# board.net
KiCad netlist of a schematic drawn in EAGLE
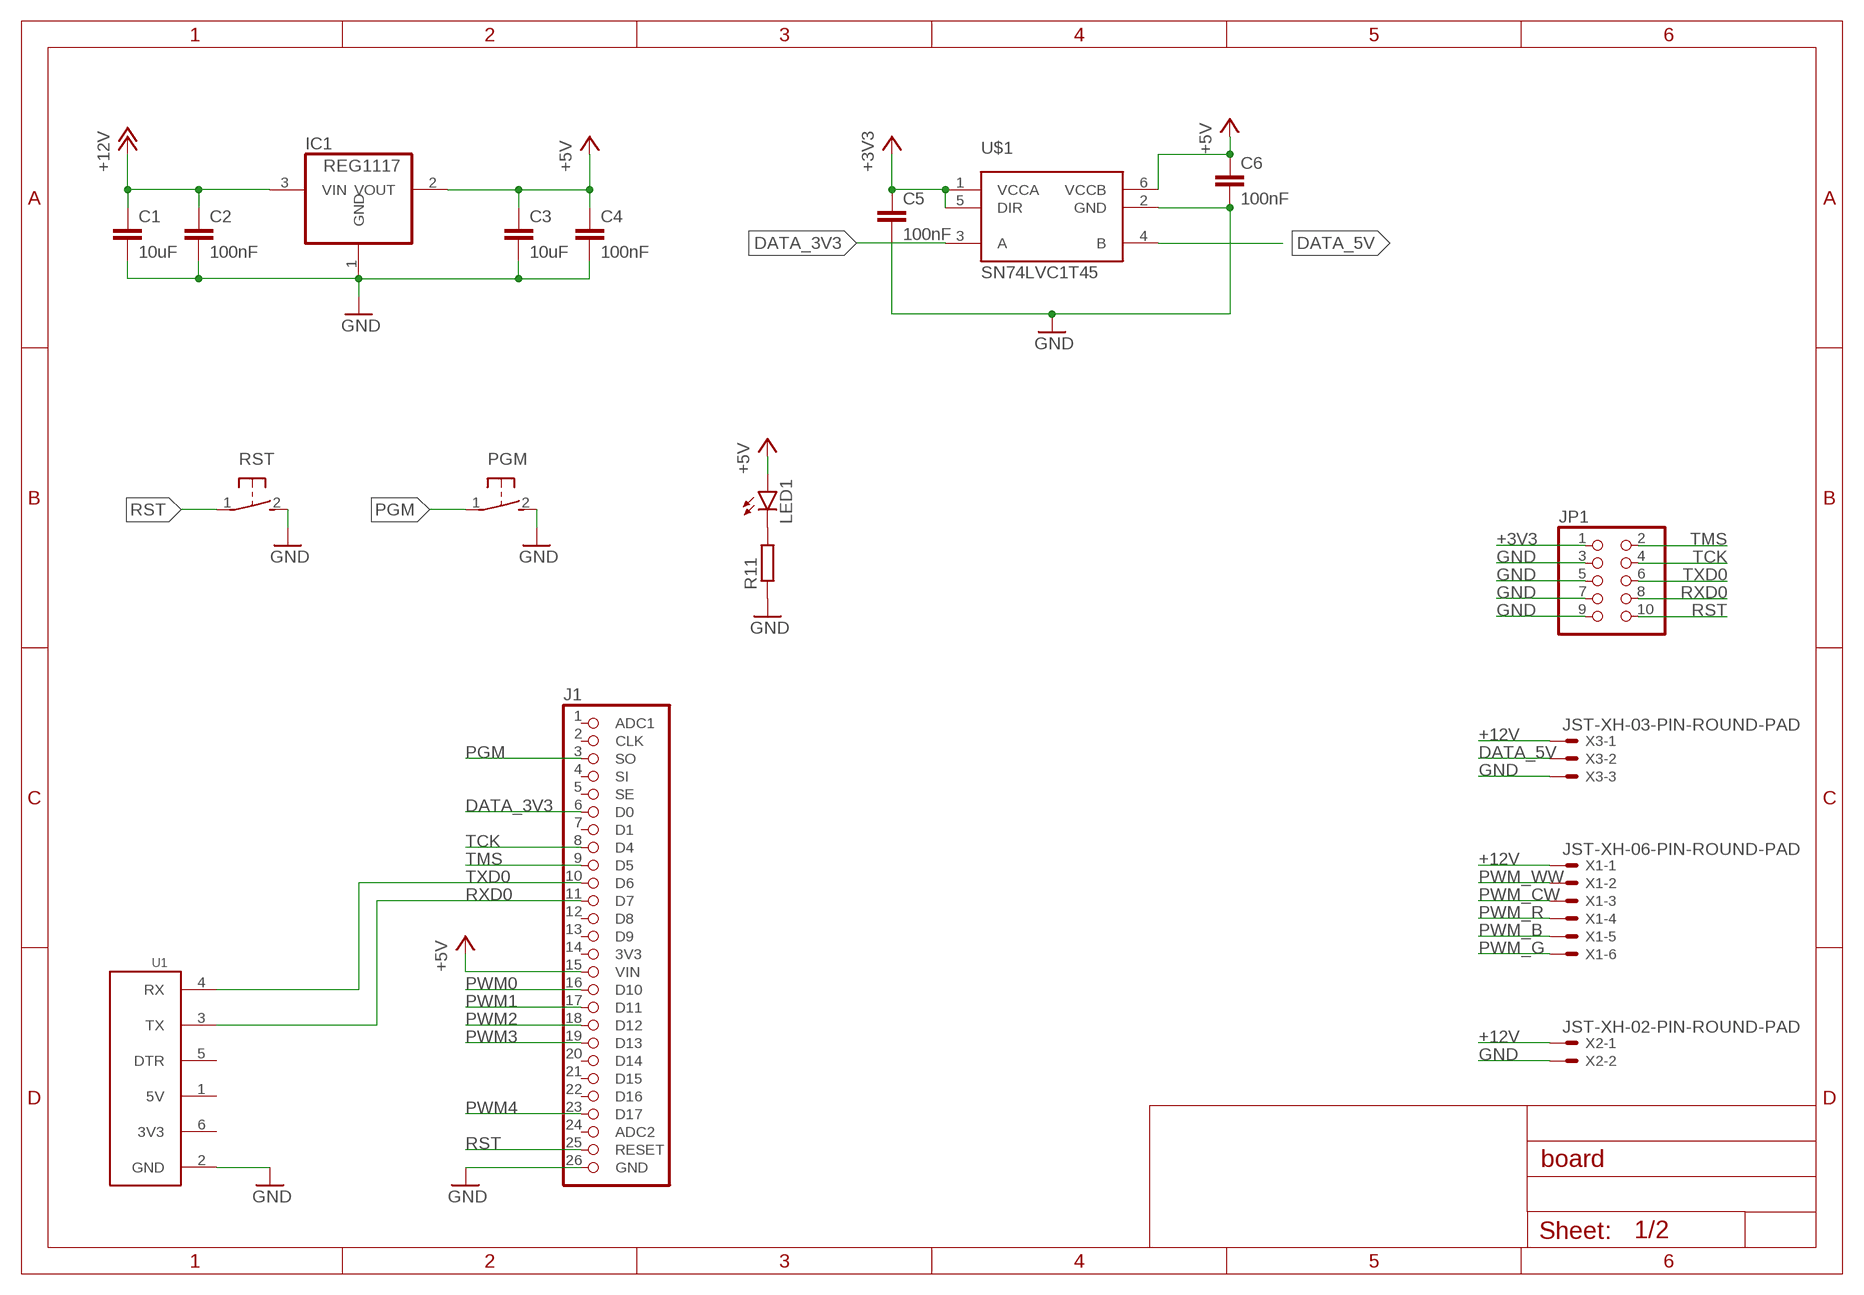
[diagram p0: schematic, sheet 1]
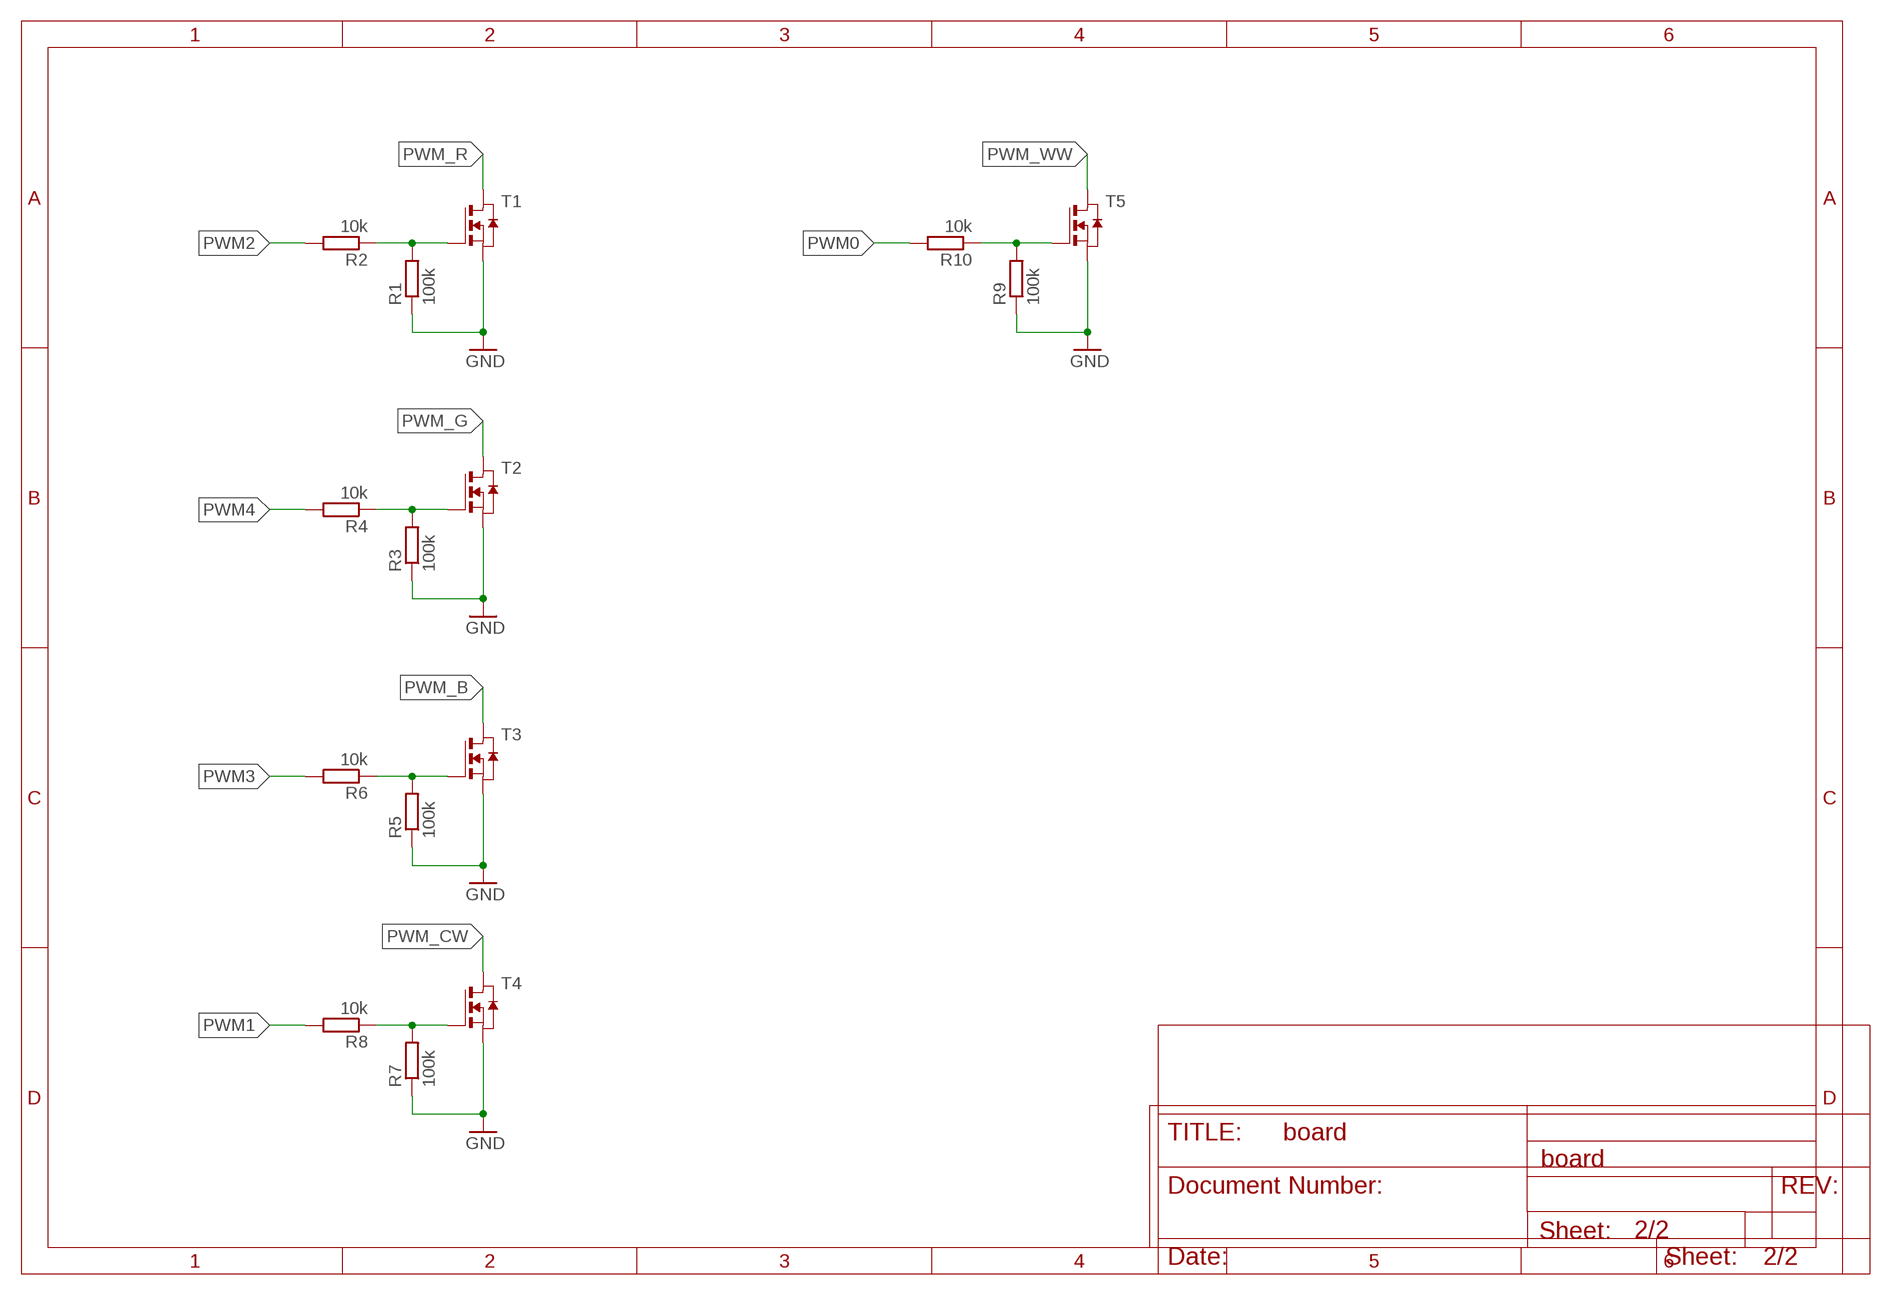
[diagram p1: schematic, sheet 2]

(export (version "E")
  (design (tool "Eeschema 10.0.6"))
  (components
    (comp (ref "C1")
      (value "10uF")
      (footprint "eagle-import:C0603")
      (libsource (lib "eagle-import") (part "C-EUC0603"))
    )
    (comp (ref "C2")
      (value "100nF")
      (footprint "eagle-import:C0603")
      (libsource (lib "eagle-import") (part "C-EUC0603"))
    )
    (comp (ref "C3")
      (value "10uF")
      (footprint "eagle-import:C0603")
      (libsource (lib "eagle-import") (part "C-EUC0603"))
    )
    (comp (ref "C4")
      (value "100nF")
      (footprint "eagle-import:C0603")
      (libsource (lib "eagle-import") (part "C-EUC0603"))
    )
    (comp (ref "C5")
      (value "100nF")
      (footprint "eagle-import:C0603")
      (libsource (lib "eagle-import") (part "C-EUC0603"))
    )
    (comp (ref "C6")
      (value "100nF")
      (footprint "eagle-import:C0603")
      (libsource (lib "eagle-import") (part "C-EUC0603"))
    )
    (comp (ref "IC1")
      (value "REG1117")
      (footprint "eagle-import:SOT223")
      (libsource (lib "eagle-import") (part "REG1117"))
    )
    (comp (ref "J1")
      (value "E75-2G4M20S-SOCKET")
      (footprint "eagle-import:E75-2G4M20S-SOCKET")
      (libsource (lib "eagle-import") (part "E75-2G4M20S-SOCKET"))
    )
    (comp (ref "JP1")
      (value "PINHD-2X5")
      (footprint "eagle-import:2X05")
      (libsource (lib "eagle-import") (part "PINHD-2X5"))
    )
    (comp (ref "LED1")
      (value "LEDCHIP-LED0603")
      (footprint "eagle-import:CHIP-LED0603")
      (libsource (lib "eagle-import") (part "LEDCHIP-LED0603"))
    )
    (comp (ref "PGM")
      (value "BUTTON3X4")
      (footprint "eagle-import:BUTTON3X4")
      (libsource (lib "eagle-import") (part "BUTTON3X4"))
    )
    (comp (ref "R11")
      (value "R-EU_R0603")
      (footprint "eagle-import:R0603")
      (libsource (lib "eagle-import") (part "R-EU_R0603"))
    )
    (comp (ref "RST")
      (value "BUTTON3X4")
      (footprint "eagle-import:BUTTON3X4")
      (libsource (lib "eagle-import") (part "BUTTON3X4"))
    )
    (comp (ref "U$1")
      (value "SN74LVC1T45")
      (footprint "eagle-import:SOT23-6")
      (fields (field (name "MF") "Texas Instruments"))
      (libsource (lib "eagle-import") (part "SN74LVC1T45"))
    )
    (comp (ref "U1")
      (value "CP2102-BOARD")
      (footprint "eagle-import:CP2102-BOARD")
      (libsource (lib "eagle-import") (part "CP2102-BOARD"))
    )
    (comp (ref "X1")
      (value "JST-XH-06-PIN-ROUND-PAD")
      (footprint "eagle-import:JST-XH-06-PACKAGE-ROUND-PAD")
      (libsource (lib "eagle-import") (part "JST-XH-06-PIN-ROUND-PAD"))
    )
    (comp (ref "X2")
      (value "JST-XH-02-PIN-ROUND-PAD")
      (footprint "eagle-import:JST-XH-02-PACKAGE-ROUND-PAD")
      (libsource (lib "eagle-import") (part "JST-XH-02-PIN-ROUND-PAD"))
    )
    (comp (ref "X3")
      (value "JST-XH-03-PIN-ROUND-PAD")
      (footprint "eagle-import:JST-XH-03-PACKAGE-ROUND-PAD")
      (libsource (lib "eagle-import") (part "JST-XH-03-PIN-ROUND-PAD"))
    )
    (comp (ref "R1")
      (value "100k")
      (footprint "eagle-import:R0603")
      (libsource (lib "eagle-import") (part "R-EU_R0603"))
    )
    (comp (ref "R2")
      (value "10k")
      (footprint "eagle-import:R0603")
      (libsource (lib "eagle-import") (part "R-EU_R0603"))
    )
    (comp (ref "R3")
      (value "100k")
      (footprint "eagle-import:R0603")
      (libsource (lib "eagle-import") (part "R-EU_R0603"))
    )
    (comp (ref "R4")
      (value "10k")
      (footprint "eagle-import:R0603")
      (libsource (lib "eagle-import") (part "R-EU_R0603"))
    )
    (comp (ref "R5")
      (value "100k")
      (footprint "eagle-import:R0603")
      (libsource (lib "eagle-import") (part "R-EU_R0603"))
    )
    (comp (ref "R6")
      (value "10k")
      (footprint "eagle-import:R0603")
      (libsource (lib "eagle-import") (part "R-EU_R0603"))
    )
    (comp (ref "R7")
      (value "100k")
      (footprint "eagle-import:R0603")
      (libsource (lib "eagle-import") (part "R-EU_R0603"))
    )
    (comp (ref "R8")
      (value "10k")
      (footprint "eagle-import:R0603")
      (libsource (lib "eagle-import") (part "R-EU_R0603"))
    )
    (comp (ref "R9")
      (value "100k")
      (footprint "eagle-import:R0603")
      (libsource (lib "eagle-import") (part "R-EU_R0603"))
    )
    (comp (ref "R10")
      (value "10k")
      (footprint "eagle-import:R0603")
      (libsource (lib "eagle-import") (part "R-EU_R0603"))
    )
    (comp (ref "T1")
      (value "NMOSSOT23")
      (footprint "eagle-import:SOT-23")
      (libsource (lib "eagle-import") (part "NMOSSOT23"))
    )
    (comp (ref "T2")
      (value "NMOSSOT23")
      (footprint "eagle-import:SOT-23")
      (libsource (lib "eagle-import") (part "NMOSSOT23"))
    )
    (comp (ref "T3")
      (value "NMOSSOT23")
      (footprint "eagle-import:SOT-23")
      (libsource (lib "eagle-import") (part "NMOSSOT23"))
    )
    (comp (ref "T4")
      (value "NMOSSOT23")
      (footprint "eagle-import:SOT-23")
      (libsource (lib "eagle-import") (part "NMOSSOT23"))
    )
    (comp (ref "T5")
      (value "NMOSSOT23")
      (footprint "eagle-import:SOT-23")
      (libsource (lib "eagle-import") (part "NMOSSOT23"))
    )
  )
  (nets
    (net (code "1") (name "+3V3") (class "Default")
      (node (ref "C5") (pin "1") (pinfunction "1_1") (pintype "passive"))
      (node (ref "JP1") (pin "1") (pinfunction "1_1") (pintype "passive"))
      (node (ref "U$1") (pin "1") (pinfunction "VCCA_1") (pintype "power_in"))
      (node (ref "U$1") (pin "5") (pinfunction "DIR_5") (pintype "input"))
    )
    (net (code "2") (name "+5V") (class "Default")
      (node (ref "C3") (pin "1") (pinfunction "1_1") (pintype "passive"))
      (node (ref "C4") (pin "1") (pinfunction "1_1") (pintype "passive"))
      (node (ref "C6") (pin "1") (pinfunction "1_1") (pintype "passive"))
      (node (ref "IC1") (pin "2") (pinfunction "VOUT_2") (pintype "output"))
      (node (ref "J1") (pin "15") (pinfunction "VIN_15") (pintype "passive"))
      (node (ref "LED1") (pin "A") (pinfunction "A_A") (pintype "passive"))
      (node (ref "U$1") (pin "6") (pinfunction "VCCB_6") (pintype "power_in"))
    )
    (net (code "3") (name "+12V") (class "Default")
      (node (ref "C1") (pin "1") (pinfunction "1_1") (pintype "passive"))
      (node (ref "C2") (pin "1") (pinfunction "1_1") (pintype "passive"))
      (node (ref "IC1") (pin "3") (pinfunction "VIN_3") (pintype "input"))
      (node (ref "X1") (pin "1") (pinfunction "S_1") (pintype "passive"))
      (node (ref "X2") (pin "1") (pinfunction "S_1") (pintype "passive"))
      (node (ref "X3") (pin "1") (pinfunction "S_1") (pintype "passive"))
    )
    (net (code "4") (name "DATA_3V3") (class "Default")
      (node (ref "J1") (pin "6") (pinfunction "D0_6") (pintype "passive"))
      (node (ref "U$1") (pin "3") (pinfunction "A_3") (pintype "bidirectional"))
    )
    (net (code "5") (name "DATA_5V") (class "Default")
      (node (ref "U$1") (pin "4") (pinfunction "B_4") (pintype "bidirectional"))
      (node (ref "X3") (pin "2") (pinfunction "S_2") (pintype "passive"))
    )
    (net (code "6") (name "GND") (class "Default")
      (node (ref "C1") (pin "2") (pinfunction "2_2") (pintype "passive"))
      (node (ref "C2") (pin "2") (pinfunction "2_2") (pintype "passive"))
      (node (ref "C3") (pin "2") (pinfunction "2_2") (pintype "passive"))
      (node (ref "C4") (pin "2") (pinfunction "2_2") (pintype "passive"))
      (node (ref "C5") (pin "2") (pinfunction "2_2") (pintype "passive"))
      (node (ref "C6") (pin "2") (pinfunction "2_2") (pintype "passive"))
      (node (ref "IC1") (pin "1") (pinfunction "GND_1") (pintype "power_in"))
      (node (ref "J1") (pin "26") (pinfunction "GND_26") (pintype "passive"))
      (node (ref "JP1") (pin "3") (pinfunction "3_3") (pintype "passive"))
      (node (ref "JP1") (pin "5") (pinfunction "5_5") (pintype "passive"))
      (node (ref "JP1") (pin "7") (pinfunction "7_7") (pintype "passive"))
      (node (ref "JP1") (pin "9") (pinfunction "9_9") (pintype "passive"))
      (node (ref "PGM") (pin "2") (pinfunction "S_2") (pintype "passive"))
      (node (ref "R1") (pin "1") (pinfunction "1_1") (pintype "passive"))
      (node (ref "R11") (pin "1") (pinfunction "1_1") (pintype "passive"))
      (node (ref "R3") (pin "1") (pinfunction "1_1") (pintype "passive"))
      (node (ref "R5") (pin "1") (pinfunction "1_1") (pintype "passive"))
      (node (ref "R7") (pin "1") (pinfunction "1_1") (pintype "passive"))
      (node (ref "R9") (pin "1") (pinfunction "1_1") (pintype "passive"))
      (node (ref "RST") (pin "2") (pinfunction "S_2") (pintype "passive"))
      (node (ref "T1") (pin "2") (pinfunction "S_2") (pintype "passive"))
      (node (ref "T2") (pin "2") (pinfunction "S_2") (pintype "passive"))
      (node (ref "T3") (pin "2") (pinfunction "S_2") (pintype "passive"))
      (node (ref "T4") (pin "2") (pinfunction "S_2") (pintype "passive"))
      (node (ref "T5") (pin "2") (pinfunction "S_2") (pintype "passive"))
      (node (ref "U$1") (pin "2") (pinfunction "GND_2") (pintype "power_in"))
      (node (ref "U1") (pin "2") (pinfunction "GND_2") (pintype "bidirectional"))
      (node (ref "X2") (pin "2") (pinfunction "S_2") (pintype "passive"))
      (node (ref "X3") (pin "3") (pinfunction "S_3") (pintype "passive"))
    )
    (net (code "7") (name "Net-(LED1-PadC)") (class "Default")
      (node (ref "LED1") (pin "C") (pinfunction "C_C") (pintype "passive"))
      (node (ref "R11") (pin "2") (pinfunction "2_2") (pintype "passive"))
    )
    (net (code "8") (name "Net-(T1-G)") (class "Default")
      (node (ref "R1") (pin "2") (pinfunction "2_2") (pintype "passive"))
      (node (ref "R2") (pin "1") (pinfunction "1_1") (pintype "passive"))
      (node (ref "T1") (pin "3") (pinfunction "G_3") (pintype "passive"))
    )
    (net (code "9") (name "Net-(T2-G)") (class "Default")
      (node (ref "R3") (pin "2") (pinfunction "2_2") (pintype "passive"))
      (node (ref "R4") (pin "1") (pinfunction "1_1") (pintype "passive"))
      (node (ref "T2") (pin "3") (pinfunction "G_3") (pintype "passive"))
    )
    (net (code "10") (name "Net-(T3-G)") (class "Default")
      (node (ref "R5") (pin "2") (pinfunction "2_2") (pintype "passive"))
      (node (ref "R6") (pin "1") (pinfunction "1_1") (pintype "passive"))
      (node (ref "T3") (pin "3") (pinfunction "G_3") (pintype "passive"))
    )
    (net (code "11") (name "Net-(T4-G)") (class "Default")
      (node (ref "R7") (pin "2") (pinfunction "2_2") (pintype "passive"))
      (node (ref "R8") (pin "1") (pinfunction "1_1") (pintype "passive"))
      (node (ref "T4") (pin "3") (pinfunction "G_3") (pintype "passive"))
    )
    (net (code "12") (name "Net-(T5-G)") (class "Default")
      (node (ref "R10") (pin "1") (pinfunction "1_1") (pintype "passive"))
      (node (ref "R9") (pin "2") (pinfunction "2_2") (pintype "passive"))
      (node (ref "T5") (pin "3") (pinfunction "G_3") (pintype "passive"))
    )
    (net (code "13") (name "PGM") (class "Default")
      (node (ref "J1") (pin "3") (pinfunction "SO_3") (pintype "passive"))
      (node (ref "PGM") (pin "1") (pinfunction "P_1") (pintype "passive"))
    )
    (net (code "14") (name "PWM0") (class "Default")
      (node (ref "J1") (pin "16") (pinfunction "D10_16") (pintype "passive"))
      (node (ref "R10") (pin "2") (pinfunction "2_2") (pintype "passive"))
    )
    (net (code "15") (name "PWM1") (class "Default")
      (node (ref "J1") (pin "17") (pinfunction "D11_17") (pintype "passive"))
      (node (ref "R8") (pin "2") (pinfunction "2_2") (pintype "passive"))
    )
    (net (code "16") (name "PWM2") (class "Default")
      (node (ref "J1") (pin "18") (pinfunction "D12_18") (pintype "passive"))
      (node (ref "R2") (pin "2") (pinfunction "2_2") (pintype "passive"))
    )
    (net (code "17") (name "PWM3") (class "Default")
      (node (ref "J1") (pin "19") (pinfunction "D13_19") (pintype "passive"))
      (node (ref "R6") (pin "2") (pinfunction "2_2") (pintype "passive"))
    )
    (net (code "18") (name "PWM4") (class "Default")
      (node (ref "J1") (pin "23") (pinfunction "D17_23") (pintype "passive"))
      (node (ref "R4") (pin "2") (pinfunction "2_2") (pintype "passive"))
    )
    (net (code "19") (name "PWM_B") (class "Default")
      (node (ref "T3") (pin "1") (pinfunction "D_1") (pintype "passive"))
      (node (ref "X1") (pin "5") (pinfunction "S_5") (pintype "passive"))
    )
    (net (code "20") (name "PWM_CW") (class "Default")
      (node (ref "T4") (pin "1") (pinfunction "D_1") (pintype "passive"))
      (node (ref "X1") (pin "3") (pinfunction "S_3") (pintype "passive"))
    )
    (net (code "21") (name "PWM_G") (class "Default")
      (node (ref "T2") (pin "1") (pinfunction "D_1") (pintype "passive"))
      (node (ref "X1") (pin "6") (pinfunction "S_6") (pintype "passive"))
    )
    (net (code "22") (name "PWM_R") (class "Default")
      (node (ref "T1") (pin "1") (pinfunction "D_1") (pintype "passive"))
      (node (ref "X1") (pin "4") (pinfunction "S_4") (pintype "passive"))
    )
    (net (code "23") (name "PWM_WW") (class "Default")
      (node (ref "T5") (pin "1") (pinfunction "D_1") (pintype "passive"))
      (node (ref "X1") (pin "2") (pinfunction "S_2") (pintype "passive"))
    )
    (net (code "24") (name "RST") (class "Default")
      (node (ref "J1") (pin "25") (pinfunction "RESET_25") (pintype "passive"))
      (node (ref "JP1") (pin "10") (pinfunction "10_10") (pintype "passive"))
      (node (ref "RST") (pin "1") (pinfunction "P_1") (pintype "passive"))
    )
    (net (code "25") (name "RXD0") (class "Default")
      (node (ref "J1") (pin "11") (pinfunction "D7_11") (pintype "passive"))
      (node (ref "JP1") (pin "8") (pinfunction "8_8") (pintype "passive"))
      (node (ref "U1") (pin "3") (pinfunction "TX_3") (pintype "bidirectional"))
    )
    (net (code "26") (name "TCK") (class "Default")
      (node (ref "J1") (pin "8") (pinfunction "D4_8") (pintype "passive"))
      (node (ref "JP1") (pin "4") (pinfunction "4_4") (pintype "passive"))
    )
    (net (code "27") (name "TMS") (class "Default")
      (node (ref "J1") (pin "9") (pinfunction "D5_9") (pintype "passive"))
      (node (ref "JP1") (pin "2") (pinfunction "2_2") (pintype "passive"))
    )
    (net (code "28") (name "TXD0") (class "Default")
      (node (ref "J1") (pin "10") (pinfunction "D6_10") (pintype "passive"))
      (node (ref "JP1") (pin "6") (pinfunction "6_6") (pintype "passive"))
      (node (ref "U1") (pin "4") (pinfunction "RX_4") (pintype "bidirectional"))
    )
    (net (code "29") (name "unconnected-(J1-3V3-Pad14)") (class "Default")
      (node (ref "J1") (pin "14") (pinfunction "3V3_14") (pintype "passive"))
    )
    (net (code "30") (name "unconnected-(J1-ADC1-Pad1)") (class "Default")
      (node (ref "J1") (pin "1") (pinfunction "ADC1_1") (pintype "passive"))
    )
    (net (code "31") (name "unconnected-(J1-ADC2-Pad24)") (class "Default")
      (node (ref "J1") (pin "24") (pinfunction "ADC2_24") (pintype "passive"))
    )
    (net (code "32") (name "unconnected-(J1-CLK-Pad2)") (class "Default")
      (node (ref "J1") (pin "2") (pinfunction "CLK_2") (pintype "passive"))
    )
    (net (code "33") (name "unconnected-(J1-D1-Pad7)") (class "Default")
      (node (ref "J1") (pin "7") (pinfunction "D1_7") (pintype "passive"))
    )
    (net (code "34") (name "unconnected-(J1-D8-Pad12)") (class "Default")
      (node (ref "J1") (pin "12") (pinfunction "D8_12") (pintype "passive"))
    )
    (net (code "35") (name "unconnected-(J1-D9-Pad13)") (class "Default")
      (node (ref "J1") (pin "13") (pinfunction "D9_13") (pintype "passive"))
    )
    (net (code "36") (name "unconnected-(J1-D14-Pad20)") (class "Default")
      (node (ref "J1") (pin "20") (pinfunction "D14_20") (pintype "passive"))
    )
    (net (code "37") (name "unconnected-(J1-D15-Pad21)") (class "Default")
      (node (ref "J1") (pin "21") (pinfunction "D15_21") (pintype "passive"))
    )
    (net (code "38") (name "unconnected-(J1-D16-Pad22)") (class "Default")
      (node (ref "J1") (pin "22") (pinfunction "D16_22") (pintype "passive"))
    )
    (net (code "39") (name "unconnected-(J1-SE-Pad5)") (class "Default")
      (node (ref "J1") (pin "5") (pinfunction "SE_5") (pintype "passive"))
    )
    (net (code "40") (name "unconnected-(J1-SI-Pad4)") (class "Default")
      (node (ref "J1") (pin "4") (pinfunction "SI_4") (pintype "passive"))
    )
    (net (code "41") (name "unconnected-(U1-3V3-Pad6)") (class "Default")
      (node (ref "U1") (pin "6") (pinfunction "3V3_6") (pintype "bidirectional"))
    )
    (net (code "42") (name "unconnected-(U1-5V-Pad1)") (class "Default")
      (node (ref "U1") (pin "1") (pinfunction "5V_1") (pintype "bidirectional"))
    )
    (net (code "43") (name "unconnected-(U1-DTR-Pad5)") (class "Default")
      (node (ref "U1") (pin "5") (pinfunction "DTR_5") (pintype "bidirectional"))
    )
  )
)
